# ERROR_DISPLAY.net
KiCad netlist of a schematic drawn in Altium Designer
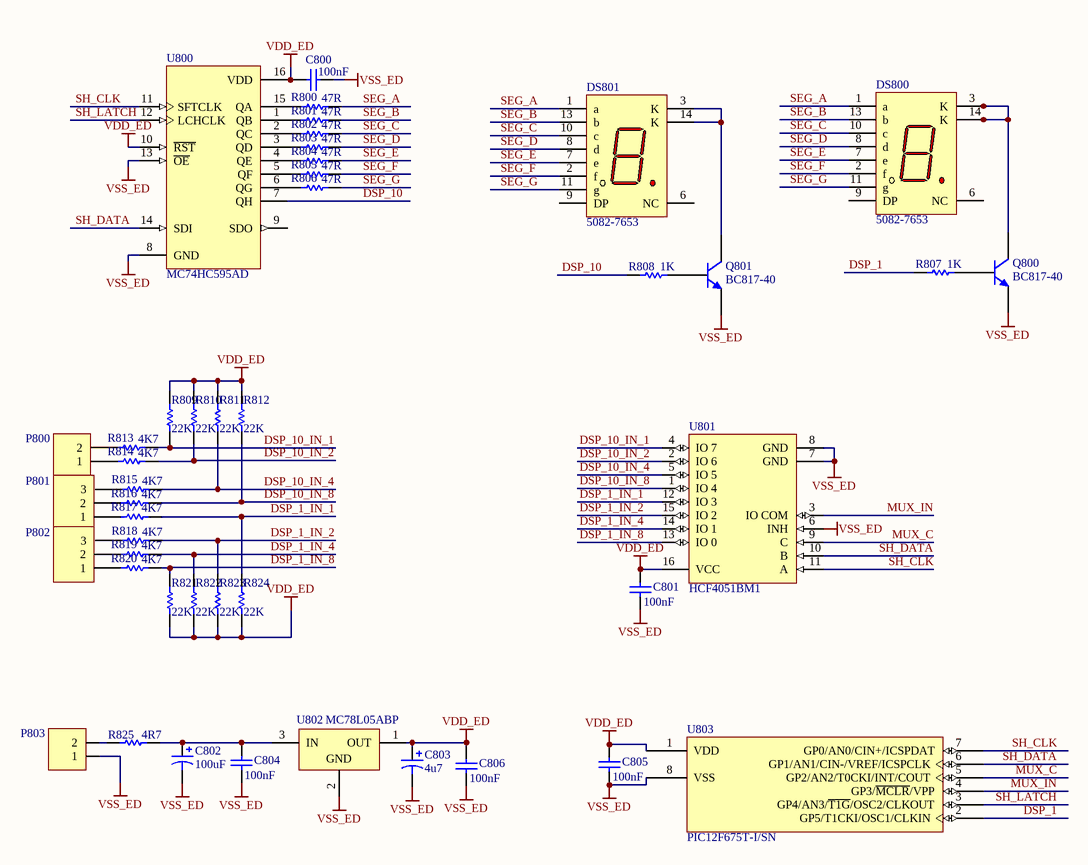
[diagram p0: ERROR_DISPLAY.SchDoc]

(export (version "E")
  (design (tool "Eeschema 10.0.6"))
  (components
    (comp (ref "C800")
      (value "100nF")
      (footprint "0805")
      (description "Ceramic Chip Capacitor - Standard")
      (fields (field (name "PUBLISHER") "Altium Limited"))
      (libsource (lib "KEMET Chip Capacitor") (part "C0805"))
    )
    (comp (ref "C801")
      (value "100nF")
      (footprint "0805")
      (description "Ceramic Chip Capacitor - Standard")
      (fields (field (name "PUBLISHER") "Altium Limited"))
      (libsource (lib "KEMET Chip Capacitor") (part "C0805"))
    )
    (comp (ref "C802")
      (value "100uF")
      (footprint "C")
      (description "Solid Aluminum Capacitor with Organic Semiconductor Electrolyte: 10uF, 25V, Bulk Pack")
      (fields (field (name "PUBLISHER") "Altium Limited"))
      (libsource (lib "Vishay Electrolytic Radial-Lead Capacitor") (part "94SC106X0025CBP"))
    )
    (comp (ref "C803")
      (value "4u7")
      (footprint "B")
      (description "Solid Aluminum Capacitor with Organic Semiconductor Electrolyte: 2.2uF, 30V, Bulk Pack")
      (fields (field (name "PUBLISHER") "Altium Limited"))
      (libsource (lib "Vishay Electrolytic Radial-Lead Capacitor") (part "94SC225X0030BBP"))
    )
    (comp (ref "C804")
      (value "100nF")
      (footprint "0805")
      (description "Ceramic Chip Capacitor - Standard")
      (fields (field (name "PUBLISHER") "Altium Limited"))
      (libsource (lib "KEMET Chip Capacitor") (part "C0805"))
    )
    (comp (ref "C805")
      (value "100nF")
      (footprint "0805")
      (description "Ceramic Chip Capacitor - Standard")
      (fields (field (name "PUBLISHER") "Altium Limited"))
      (libsource (lib "KEMET Chip Capacitor") (part "C0805"))
    )
    (comp (ref "C806")
      (value "100nF")
      (footprint "0805")
      (description "Ceramic Chip Capacitor - Standard")
      (fields (field (name "PUBLISHER") "Altium Limited"))
      (libsource (lib "KEMET Chip Capacitor") (part "C0805"))
    )
    (comp (ref "DS800")
      (value "5082-7653")
      (footprint "E-11(R)")
      (description "10.92 mm HER 7-Segment Display: CC, RH DP")
      (fields (field (name "PUBLISHER") "Altium Limited"))
      (libsource (lib "Agilent LED Display 7-Segment, 1-Digit") (part "5082-7653"))
    )
    (comp (ref "DS801")
      (value "5082-7653")
      (footprint "E-11(R)")
      (description "10.92 mm HER 7-Segment Display: CC, RH DP")
      (fields (field (name "PUBLISHER") "Altium Limited"))
      (libsource (lib "Agilent LED Display 7-Segment, 1-Digit") (part "5082-7653"))
    )
    (comp (ref "P800")
      (value "~")
      (footprint "TERMINAL BLOK 2")
      (description "Terminal blok 2")
      (libsource (lib "TERMINAL_CONNECOR_2") (part "Terminal blok 2 pina"))
    )
    (comp (ref "P801")
      (value "~")
      (footprint "TERMINAL BLOK")
      (description "Terminal blok")
      (libsource (lib "TERMINAL_CONNECOR_3") (part "Terminal blok 3 pina"))
    )
    (comp (ref "P802")
      (value "~")
      (footprint "TERMINAL BLOK")
      (description "Terminal blok")
      (libsource (lib "") (part "Terminal blok 3 pina_1"))
    )
    (comp (ref "P803")
      (value "~")
      (footprint "TERMINAL BLOK 2")
      (description "Terminal blok 2")
      (libsource (lib "") (part "Terminal blok 2 pina_1"))
    )
    (comp (ref "Q800")
      (value "BC817-40")
      (footprint "SOT23_N")
      (description "NPN General-purpose Transistor")
      (fields (field (name "PUBLISHER") "Altium Limited"))
      (libsource (lib "Philips Discrete BJT - Low Power") (part "BC817-40"))
    )
    (comp (ref "Q801")
      (value "BC817-40")
      (footprint "SOT23_N")
      (description "NPN General-purpose Transistor")
      (fields (field (name "PUBLISHER") "Altium Limited"))
      (libsource (lib "Philips Discrete BJT - Low Power") (part "BC817-40"))
    )
    (comp (ref "R800")
      (value "47R")
      (footprint "ERA-0603")
      (fields (field (name "PUBLISHER") "Altium Limited"))
      (libsource (lib "Panasonic Resistor") (part "ERA3Y"))
    )
    (comp (ref "R801")
      (value "47R")
      (footprint "ERA-0603")
      (fields (field (name "PUBLISHER") "Altium Limited"))
      (libsource (lib "Panasonic Resistor") (part "ERA3Y"))
    )
    (comp (ref "R802")
      (value "47R")
      (footprint "ERA-0603")
      (fields (field (name "PUBLISHER") "Altium Limited"))
      (libsource (lib "Panasonic Resistor") (part "ERA3Y"))
    )
    (comp (ref "R803")
      (value "47R")
      (footprint "ERA-0603")
      (fields (field (name "PUBLISHER") "Altium Limited"))
      (libsource (lib "Panasonic Resistor") (part "ERA3Y"))
    )
    (comp (ref "R804")
      (value "47R")
      (footprint "ERA-0603")
      (fields (field (name "PUBLISHER") "Altium Limited"))
      (libsource (lib "Panasonic Resistor") (part "ERA3Y"))
    )
    (comp (ref "R805")
      (value "47R")
      (footprint "ERA-0603")
      (fields (field (name "PUBLISHER") "Altium Limited"))
      (libsource (lib "Panasonic Resistor") (part "ERA3Y"))
    )
    (comp (ref "R806")
      (value "47R")
      (footprint "ERA-0603")
      (fields (field (name "PUBLISHER") "Altium Limited"))
      (libsource (lib "Panasonic Resistor") (part "ERA3Y"))
    )
    (comp (ref "R807")
      (value "1K")
      (footprint "ERA-0603")
      (fields (field (name "PUBLISHER") "Altium Limited"))
      (libsource (lib "Panasonic Resistor") (part "ERA3Y"))
    )
    (comp (ref "R808")
      (value "1K")
      (footprint "ERA-0603")
      (fields (field (name "PUBLISHER") "Altium Limited"))
      (libsource (lib "Panasonic Resistor") (part "ERA3Y"))
    )
    (comp (ref "R809")
      (value "22K")
      (footprint "ERA-0603")
      (fields (field (name "PUBLISHER") "Altium Limited"))
      (libsource (lib "Panasonic Resistor") (part "ERA3Y"))
    )
    (comp (ref "R810")
      (value "22K")
      (footprint "ERA-0603")
      (fields (field (name "PUBLISHER") "Altium Limited"))
      (libsource (lib "Panasonic Resistor") (part "ERA3Y"))
    )
    (comp (ref "R811")
      (value "22K")
      (footprint "ERA-0603")
      (fields (field (name "PUBLISHER") "Altium Limited"))
      (libsource (lib "Panasonic Resistor") (part "ERA3Y"))
    )
    (comp (ref "R812")
      (value "22K")
      (footprint "ERA-0603")
      (fields (field (name "PUBLISHER") "Altium Limited"))
      (libsource (lib "Panasonic Resistor") (part "ERA3Y"))
    )
    (comp (ref "R813")
      (value "4K7")
      (footprint "ERA-0603")
      (fields (field (name "PUBLISHER") "Altium Limited"))
      (libsource (lib "Panasonic Resistor") (part "ERA3Y"))
    )
    (comp (ref "R814")
      (value "4K7")
      (footprint "ERA-0603")
      (fields (field (name "PUBLISHER") "Altium Limited"))
      (libsource (lib "Panasonic Resistor") (part "ERA3Y"))
    )
    (comp (ref "R815")
      (value "4K7")
      (footprint "ERA-0603")
      (fields (field (name "PUBLISHER") "Altium Limited"))
      (libsource (lib "Panasonic Resistor") (part "ERA3Y"))
    )
    (comp (ref "R816")
      (value "4K7")
      (footprint "ERA-0603")
      (fields (field (name "PUBLISHER") "Altium Limited"))
      (libsource (lib "Panasonic Resistor") (part "ERA3Y"))
    )
    (comp (ref "R817")
      (value "4K7")
      (footprint "ERA-0603")
      (fields (field (name "PUBLISHER") "Altium Limited"))
      (libsource (lib "Panasonic Resistor") (part "ERA3Y"))
    )
    (comp (ref "R818")
      (value "4K7")
      (footprint "ERA-0603")
      (fields (field (name "PUBLISHER") "Altium Limited"))
      (libsource (lib "Panasonic Resistor") (part "ERA3Y"))
    )
    (comp (ref "R819")
      (value "4K7")
      (footprint "ERA-0603")
      (fields (field (name "PUBLISHER") "Altium Limited"))
      (libsource (lib "Panasonic Resistor") (part "ERA3Y"))
    )
    (comp (ref "R820")
      (value "4K7")
      (footprint "ERA-0603")
      (fields (field (name "PUBLISHER") "Altium Limited"))
      (libsource (lib "Panasonic Resistor") (part "ERA3Y"))
    )
    (comp (ref "R821")
      (value "22K")
      (footprint "ERA-0603")
      (fields (field (name "PUBLISHER") "Altium Limited"))
      (libsource (lib "Panasonic Resistor") (part "ERA3Y"))
    )
    (comp (ref "R822")
      (value "22K")
      (footprint "ERA-0603")
      (fields (field (name "PUBLISHER") "Altium Limited"))
      (libsource (lib "Panasonic Resistor") (part "ERA3Y"))
    )
    (comp (ref "R823")
      (value "22K")
      (footprint "ERA-0603")
      (fields (field (name "PUBLISHER") "Altium Limited"))
      (libsource (lib "Panasonic Resistor") (part "ERA3Y"))
    )
    (comp (ref "R824")
      (value "22K")
      (footprint "ERA-0603")
      (fields (field (name "PUBLISHER") "Altium Limited"))
      (libsource (lib "Panasonic Resistor") (part "ERA3Y"))
    )
    (comp (ref "R825")
      (value "4R7")
      (footprint "RD3.2x1.7")
      (fields (field (name "PUBLISHER") "Altium Limited"))
      (libsource (lib "Panasonic Resistor") (part "ERD6FC"))
    )
    (comp (ref "U800")
      (value "MC74HC595AD")
      (footprint "751B-05_N")
      (description "8-Bit Serial-Input/Serial or Prallel-Output Shift Register with Latched 3-State Outputs")
      (fields (field (name "PUBLISHER") "Altium Limited"))
      (libsource (lib "ON Semi Logic Register") (part "MC74HC595AD"))
    )
    (comp (ref "U801")
      (value "HCF4051BM1")
      (footprint "SO16_N")
      (description "Analog Multiplexer/Demultiplexer")
      (fields (field (name "PUBLISHER") "Altium Limited"))
      (libsource (lib "ST Logic Multiplexer") (part "HCF4051BM1"))
    )
    (comp (ref "U802")
      (value "MC78L05ABP")
      (footprint "29-04")
      (description "Three-Terminal Low Current Positive Voltage Regulator")
      (fields (field (name "PUBLISHER") "Altium Limited"))
      (libsource (lib "ON Semi Power Mgt Voltage Regulator") (part "MC78L05ABP"))
    )
    (comp (ref "U803")
      (value "PIC12F675T-I/SN")
      (footprint "SOIC-SN8_N")
      (fields (field (name "PUBLISHER") "Altium Limited"))
      (libsource (lib "Microchip Microcontroller 8-Bit PIC12") (part "PIC12F675T-I/SN"))
    )
  )
  (nets
    (net (code "1") (name "/DSP_1") (class "Default")
      (node (ref "R807") (pin "1") (pinfunction "1_1") (pintype "passive"))
      (node (ref "U803") (pin "2") (pinfunction "GP5/T1CKI/OSC1/CLKIN_2") (pintype "bidirectional"))
    )
    (net (code "2") (name "/DSP_1_IN_1") (class "Default")
      (node (ref "R817") (pin "2") (pinfunction "2_2") (pintype "passive"))
      (node (ref "R824") (pin "2") (pinfunction "2_2") (pintype "passive"))
      (node (ref "U801") (pin "12") (pinfunction "IO_3_12") (pintype "bidirectional"))
    )
    (net (code "3") (name "/DSP_1_IN_2") (class "Default")
      (node (ref "R818") (pin "2") (pinfunction "2_2") (pintype "passive"))
      (node (ref "R823") (pin "2") (pinfunction "2_2") (pintype "passive"))
      (node (ref "U801") (pin "15") (pinfunction "IO_2_15") (pintype "bidirectional"))
    )
    (net (code "4") (name "/DSP_1_IN_4") (class "Default")
      (node (ref "R819") (pin "2") (pinfunction "2_2") (pintype "passive"))
      (node (ref "R822") (pin "2") (pinfunction "2_2") (pintype "passive"))
      (node (ref "U801") (pin "14") (pinfunction "IO_1_14") (pintype "bidirectional"))
    )
    (net (code "5") (name "/DSP_1_IN_8") (class "Default")
      (node (ref "R820") (pin "2") (pinfunction "2_2") (pintype "passive"))
      (node (ref "R821") (pin "2") (pinfunction "2_2") (pintype "passive"))
      (node (ref "U801") (pin "13") (pinfunction "IO_0_13") (pintype "bidirectional"))
    )
    (net (code "6") (name "/DSP_10") (class "Default")
      (node (ref "R808") (pin "1") (pinfunction "1_1") (pintype "passive"))
      (node (ref "U800") (pin "7") (pinfunction "QH_7") (pintype "tri_state"))
    )
    (net (code "7") (name "/DSP_10_IN_1") (class "Default")
      (node (ref "R809") (pin "1") (pinfunction "1_1") (pintype "passive"))
      (node (ref "R813") (pin "2") (pinfunction "2_2") (pintype "passive"))
      (node (ref "U801") (pin "4") (pinfunction "IO_7_4") (pintype "bidirectional"))
    )
    (net (code "8") (name "/DSP_10_IN_2") (class "Default")
      (node (ref "R810") (pin "1") (pinfunction "1_1") (pintype "passive"))
      (node (ref "R814") (pin "2") (pinfunction "2_2") (pintype "passive"))
      (node (ref "U801") (pin "2") (pinfunction "IO_6_2") (pintype "bidirectional"))
    )
    (net (code "9") (name "/DSP_10_IN_4") (class "Default")
      (node (ref "R811") (pin "1") (pinfunction "1_1") (pintype "passive"))
      (node (ref "R815") (pin "2") (pinfunction "2_2") (pintype "passive"))
      (node (ref "U801") (pin "5") (pinfunction "IO_5_5") (pintype "bidirectional"))
    )
    (net (code "10") (name "/DSP_10_IN_8") (class "Default")
      (node (ref "R812") (pin "1") (pinfunction "1_1") (pintype "passive"))
      (node (ref "R816") (pin "2") (pinfunction "2_2") (pintype "passive"))
      (node (ref "U801") (pin "1") (pinfunction "IO_4_1") (pintype "bidirectional"))
    )
    (net (code "11") (name "/MUX_C") (class "Default")
      (node (ref "U801") (pin "9") (pinfunction "C_9") (pintype "input"))
      (node (ref "U803") (pin "5") (pinfunction "GP2/AN2/T0CKI/INT/COUT_5") (pintype "bidirectional"))
    )
    (net (code "12") (name "/MUX_IN") (class "Default")
      (node (ref "U801") (pin "3") (pinfunction "IO_COM_3") (pintype "bidirectional"))
      (node (ref "U803") (pin "4") (pinfunction "GP3/~{MCLR}/VPP_4") (pintype "bidirectional"))
    )
    (net (code "13") (name "/SEG_A") (class "Default")
      (node (ref "DS800") (pin "1") (pinfunction "a_1") (pintype "passive"))
      (node (ref "DS801") (pin "1") (pinfunction "a_1") (pintype "passive"))
      (node (ref "R800") (pin "2") (pinfunction "2_2") (pintype "passive"))
    )
    (net (code "14") (name "/SEG_B") (class "Default")
      (node (ref "DS800") (pin "13") (pinfunction "b_13") (pintype "passive"))
      (node (ref "DS801") (pin "13") (pinfunction "b_13") (pintype "passive"))
      (node (ref "R801") (pin "2") (pinfunction "2_2") (pintype "passive"))
    )
    (net (code "15") (name "/SEG_C") (class "Default")
      (node (ref "DS800") (pin "10") (pinfunction "c_10") (pintype "passive"))
      (node (ref "DS801") (pin "10") (pinfunction "c_10") (pintype "passive"))
      (node (ref "R802") (pin "2") (pinfunction "2_2") (pintype "passive"))
    )
    (net (code "16") (name "/SEG_D") (class "Default")
      (node (ref "DS800") (pin "8") (pinfunction "d_8") (pintype "passive"))
      (node (ref "DS801") (pin "8") (pinfunction "d_8") (pintype "passive"))
      (node (ref "R803") (pin "2") (pinfunction "2_2") (pintype "passive"))
    )
    (net (code "17") (name "/SEG_E") (class "Default")
      (node (ref "DS800") (pin "7") (pinfunction "e_7") (pintype "passive"))
      (node (ref "DS801") (pin "7") (pinfunction "e_7") (pintype "passive"))
      (node (ref "R804") (pin "2") (pinfunction "2_2") (pintype "passive"))
    )
    (net (code "18") (name "/SEG_F") (class "Default")
      (node (ref "DS800") (pin "2") (pinfunction "f_2") (pintype "passive"))
      (node (ref "DS801") (pin "2") (pinfunction "f_2") (pintype "passive"))
      (node (ref "R805") (pin "2") (pinfunction "2_2") (pintype "passive"))
    )
    (net (code "19") (name "/SEG_G") (class "Default")
      (node (ref "DS800") (pin "11") (pinfunction "g_11") (pintype "passive"))
      (node (ref "DS801") (pin "11") (pinfunction "g_11") (pintype "passive"))
      (node (ref "R806") (pin "2") (pinfunction "2_2") (pintype "passive"))
    )
    (net (code "20") (name "/SH_CLK") (class "Default")
      (node (ref "U800") (pin "11") (pinfunction "SFTCLK_11") (pintype "input"))
      (node (ref "U801") (pin "11") (pinfunction "A_11") (pintype "input"))
      (node (ref "U803") (pin "7") (pinfunction "GP0/AN0/CIN+/ICSPDAT_7") (pintype "bidirectional"))
    )
    (net (code "21") (name "/SH_DATA") (class "Default")
      (node (ref "U800") (pin "14") (pinfunction "SDI_14") (pintype "input"))
      (node (ref "U801") (pin "10") (pinfunction "B_10") (pintype "input"))
      (node (ref "U803") (pin "6") (pinfunction "GP1/AN1/CIN-/VREF/ICSPCLK_6") (pintype "bidirectional"))
    )
    (net (code "22") (name "/SH_LATCH") (class "Default")
      (node (ref "U800") (pin "12") (pinfunction "LCHCLK_12") (pintype "input"))
      (node (ref "U803") (pin "3") (pinfunction "GP4/AN3/~{T1G}/OSC2/CLKOUT_3") (pintype "bidirectional"))
    )
    (net (code "23") (name "Net-(P800-Pad1)") (class "Default")
      (node (ref "P800") (pin "1") (pinfunction "1_1") (pintype "passive"))
      (node (ref "R814") (pin "1") (pinfunction "1_1") (pintype "passive"))
    )
    (net (code "24") (name "Net-(P800-Pad2)") (class "Default")
      (node (ref "P800") (pin "2") (pinfunction "2_2") (pintype "passive"))
      (node (ref "R813") (pin "1") (pinfunction "1_1") (pintype "passive"))
    )
    (net (code "25") (name "Net-(P801-Pad1)") (class "Default")
      (node (ref "P801") (pin "1") (pinfunction "1_1") (pintype "passive"))
      (node (ref "R817") (pin "1") (pinfunction "1_1") (pintype "passive"))
    )
    (net (code "26") (name "Net-(P801-Pad2)") (class "Default")
      (node (ref "P801") (pin "2") (pinfunction "2_2") (pintype "passive"))
      (node (ref "R816") (pin "1") (pinfunction "1_1") (pintype "passive"))
    )
    (net (code "27") (name "Net-(P801-Pad3)") (class "Default")
      (node (ref "P801") (pin "3") (pinfunction "3_3") (pintype "passive"))
      (node (ref "R815") (pin "1") (pinfunction "1_1") (pintype "passive"))
    )
    (net (code "28") (name "Net-(P802-Pad1)") (class "Default")
      (node (ref "P802") (pin "1") (pinfunction "1_1") (pintype "passive"))
      (node (ref "R820") (pin "1") (pinfunction "1_1") (pintype "passive"))
    )
    (net (code "29") (name "Net-(P802-Pad2)") (class "Default")
      (node (ref "P802") (pin "2") (pinfunction "2_2") (pintype "passive"))
      (node (ref "R819") (pin "1") (pinfunction "1_1") (pintype "passive"))
    )
    (net (code "30") (name "Net-(P802-Pad3)") (class "Default")
      (node (ref "P802") (pin "3") (pinfunction "3_3") (pintype "passive"))
      (node (ref "R818") (pin "1") (pinfunction "1_1") (pintype "passive"))
    )
    (net (code "31") (name "Net-(P803-Pad2)") (class "Default")
      (node (ref "P803") (pin "2") (pinfunction "2_2") (pintype "passive"))
      (node (ref "R825") (pin "1") (pinfunction "1_1") (pintype "passive"))
    )
    (net (code "32") (name "Net-(Q800-B)") (class "Default")
      (node (ref "Q800") (pin "1") (pinfunction "B_1") (pintype "passive"))
      (node (ref "R807") (pin "2") (pinfunction "2_2") (pintype "passive"))
    )
    (net (code "33") (name "Net-(Q800-C)") (class "Default")
      (node (ref "DS800") (pin "14") (pinfunction "K_14") (pintype "passive"))
      (node (ref "DS800") (pin "3") (pinfunction "K_3") (pintype "passive"))
      (node (ref "Q800") (pin "3") (pinfunction "C_3") (pintype "passive"))
    )
    (net (code "34") (name "Net-(Q801-B)") (class "Default")
      (node (ref "Q801") (pin "1") (pinfunction "B_1") (pintype "passive"))
      (node (ref "R808") (pin "2") (pinfunction "2_2") (pintype "passive"))
    )
    (net (code "35") (name "Net-(Q801-C)") (class "Default")
      (node (ref "DS801") (pin "14") (pinfunction "K_14") (pintype "passive"))
      (node (ref "DS801") (pin "3") (pinfunction "K_3") (pintype "passive"))
      (node (ref "Q801") (pin "3") (pinfunction "C_3") (pintype "passive"))
    )
    (net (code "36") (name "Net-(U800-QA)") (class "Default")
      (node (ref "R800") (pin "1") (pinfunction "1_1") (pintype "passive"))
      (node (ref "U800") (pin "15") (pinfunction "QA_15") (pintype "tri_state"))
    )
    (net (code "37") (name "Net-(U800-QB)") (class "Default")
      (node (ref "R801") (pin "1") (pinfunction "1_1") (pintype "passive"))
      (node (ref "U800") (pin "1") (pinfunction "QB_1") (pintype "tri_state"))
    )
    (net (code "38") (name "Net-(U800-QC)") (class "Default")
      (node (ref "R802") (pin "1") (pinfunction "1_1") (pintype "passive"))
      (node (ref "U800") (pin "2") (pinfunction "QC_2") (pintype "tri_state"))
    )
    (net (code "39") (name "Net-(U800-QD)") (class "Default")
      (node (ref "R803") (pin "1") (pinfunction "1_1") (pintype "passive"))
      (node (ref "U800") (pin "3") (pinfunction "QD_3") (pintype "tri_state"))
    )
    (net (code "40") (name "Net-(U800-QE)") (class "Default")
      (node (ref "R804") (pin "1") (pinfunction "1_1") (pintype "passive"))
      (node (ref "U800") (pin "4") (pinfunction "QE_4") (pintype "tri_state"))
    )
    (net (code "41") (name "Net-(U800-QF)") (class "Default")
      (node (ref "R805") (pin "1") (pinfunction "1_1") (pintype "passive"))
      (node (ref "U800") (pin "5") (pinfunction "QF_5") (pintype "tri_state"))
    )
    (net (code "42") (name "Net-(U800-QG)") (class "Default")
      (node (ref "R806") (pin "1") (pinfunction "1_1") (pintype "passive"))
      (node (ref "U800") (pin "6") (pinfunction "QG_6") (pintype "tri_state"))
    )
    (net (code "43") (name "Net-(U802-IN)") (class "Default")
      (node (ref "C802") (pin "1") (pinfunction "1_1") (pintype "passive"))
      (node (ref "C804") (pin "1") (pinfunction "1_1") (pintype "passive"))
      (node (ref "R825") (pin "2") (pinfunction "2_2") (pintype "passive"))
      (node (ref "U802") (pin "3") (pinfunction "IN_3") (pintype "power_in"))
    )
    (net (code "44") (name "VDD_ED") (class "Default")
      (node (ref "C800") (pin "2") (pinfunction "2_2") (pintype "passive"))
      (node (ref "C801") (pin "1") (pinfunction "1_1") (pintype "passive"))
      (node (ref "C803") (pin "1") (pinfunction "1_1") (pintype "passive"))
      (node (ref "C805") (pin "1") (pinfunction "1_1") (pintype "passive"))
      (node (ref "C806") (pin "1") (pinfunction "1_1") (pintype "passive"))
      (node (ref "R809") (pin "2") (pinfunction "2_2") (pintype "passive"))
      (node (ref "R810") (pin "2") (pinfunction "2_2") (pintype "passive"))
      (node (ref "R811") (pin "2") (pinfunction "2_2") (pintype "passive"))
      (node (ref "R812") (pin "2") (pinfunction "2_2") (pintype "passive"))
      (node (ref "R821") (pin "1") (pinfunction "1_1") (pintype "passive"))
      (node (ref "R822") (pin "1") (pinfunction "1_1") (pintype "passive"))
      (node (ref "R823") (pin "1") (pinfunction "1_1") (pintype "passive"))
      (node (ref "R824") (pin "1") (pinfunction "1_1") (pintype "passive"))
      (node (ref "U800") (pin "10") (pinfunction "~{RST}_10") (pintype "input"))
      (node (ref "U800") (pin "16") (pinfunction "VDD_16") (pintype "power_in"))
      (node (ref "U801") (pin "16") (pinfunction "VCC_16") (pintype "power_in"))
      (node (ref "U802") (pin "1") (pinfunction "OUT_1") (pintype "power_in"))
      (node (ref "U803") (pin "1") (pinfunction "VDD_1") (pintype "power_in"))
    )
    (net (code "45") (name "VSS_ED") (class "Default")
      (node (ref "C800") (pin "1") (pinfunction "1_1") (pintype "passive"))
      (node (ref "C801") (pin "2") (pinfunction "2_2") (pintype "passive"))
      (node (ref "C802") (pin "2") (pinfunction "2_2") (pintype "passive"))
      (node (ref "C803") (pin "2") (pinfunction "2_2") (pintype "passive"))
      (node (ref "C804") (pin "2") (pinfunction "2_2") (pintype "passive"))
      (node (ref "C805") (pin "2") (pinfunction "2_2") (pintype "passive"))
      (node (ref "C806") (pin "2") (pinfunction "2_2") (pintype "passive"))
      (node (ref "P803") (pin "1") (pinfunction "1_1") (pintype "passive"))
      (node (ref "Q800") (pin "2") (pinfunction "E_2") (pintype "passive"))
      (node (ref "Q801") (pin "2") (pinfunction "E_2") (pintype "passive"))
      (node (ref "U800") (pin "13") (pinfunction "~{OE}_13") (pintype "input"))
      (node (ref "U800") (pin "8") (pinfunction "GND_8") (pintype "power_in"))
      (node (ref "U801") (pin "6") (pinfunction "INH_6") (pintype "input"))
      (node (ref "U801") (pin "7") (pinfunction "GND_7") (pintype "power_in"))
      (node (ref "U801") (pin "8") (pinfunction "GND_8") (pintype "power_in"))
      (node (ref "U802") (pin "2") (pinfunction "GND_2") (pintype "power_in"))
      (node (ref "U803") (pin "8") (pinfunction "VSS_8") (pintype "power_in"))
    )
    (net (code "46") (name "unconnected-(DS800-DP-Pad9)") (class "Default")
      (node (ref "DS800") (pin "9") (pinfunction "DP_9") (pintype "passive"))
    )
    (net (code "47") (name "unconnected-(DS800-NC-Pad6)") (class "Default")
      (node (ref "DS800") (pin "6") (pinfunction "NC_6") (pintype "passive"))
    )
    (net (code "48") (name "unconnected-(DS801-DP-Pad9)") (class "Default")
      (node (ref "DS801") (pin "9") (pinfunction "DP_9") (pintype "passive"))
    )
    (net (code "49") (name "unconnected-(DS801-NC-Pad6)") (class "Default")
      (node (ref "DS801") (pin "6") (pinfunction "NC_6") (pintype "passive"))
    )
    (net (code "50") (name "unconnected-(U800-SDO-Pad9)") (class "Default")
      (node (ref "U800") (pin "9") (pinfunction "SDO_9") (pintype "output"))
    )
  )
)
